# untitled.net
KiCad netlist of a schematic drawn in EAGLE
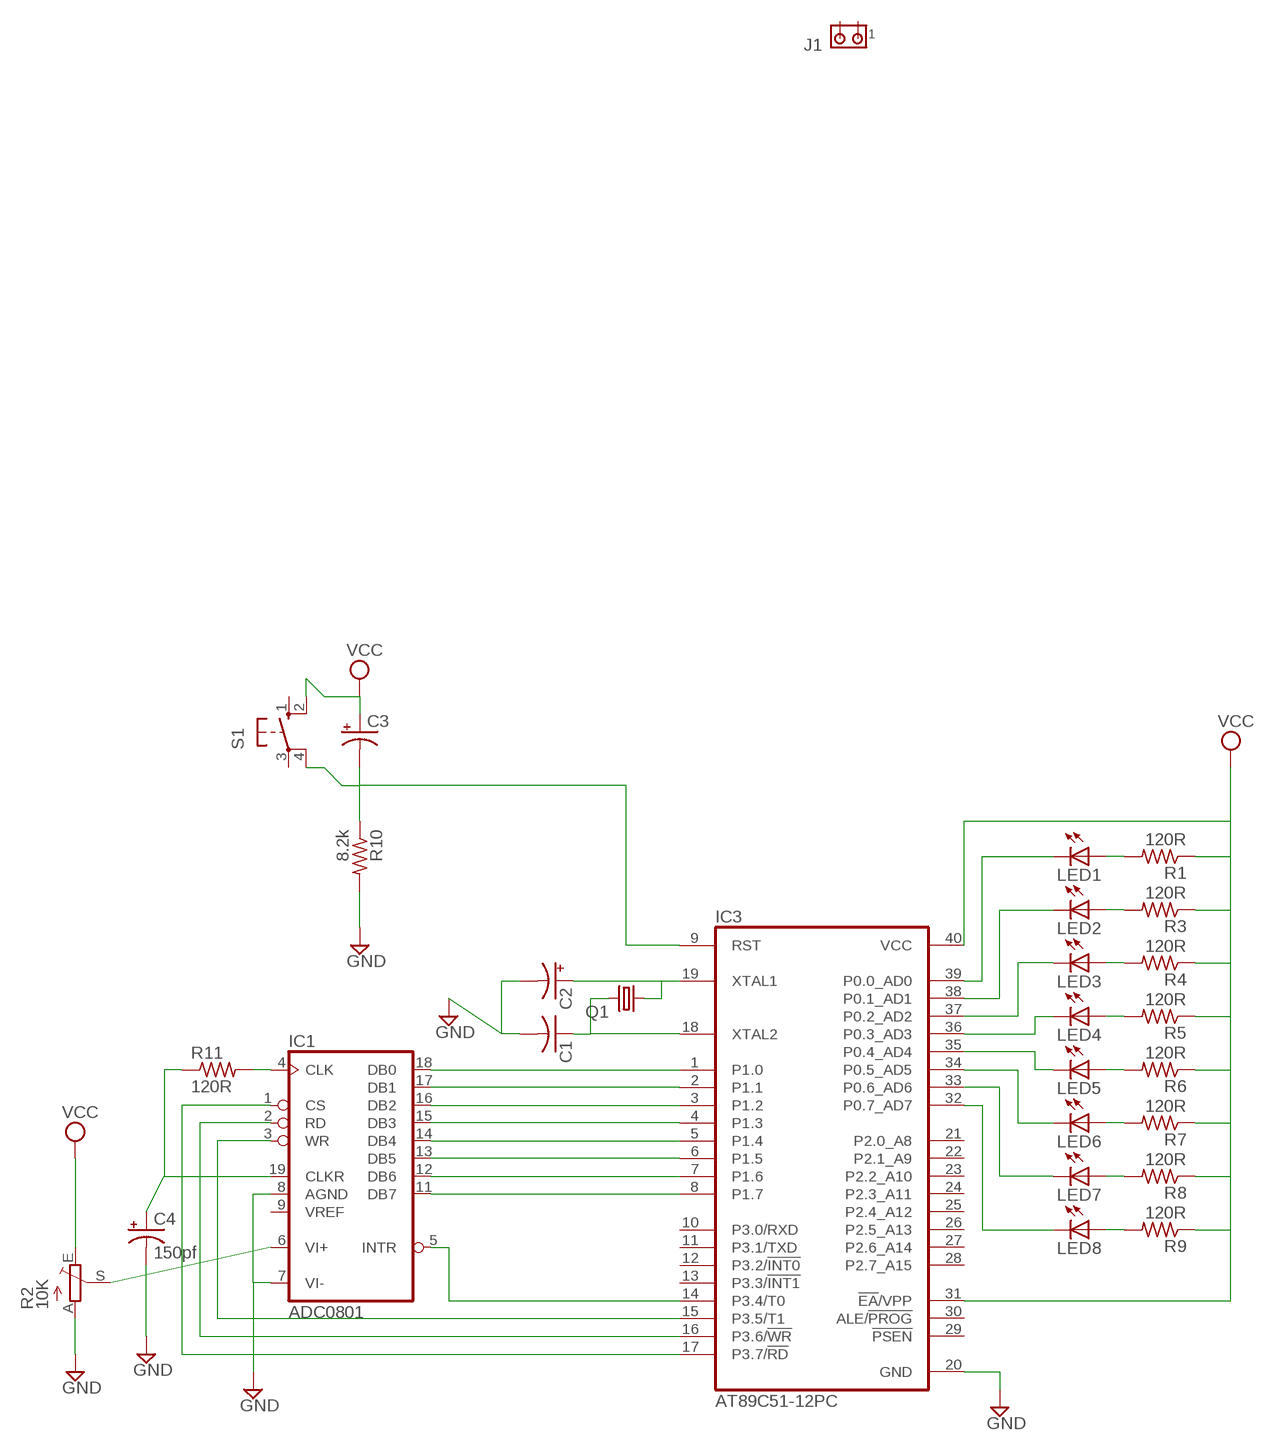
[diagram p0: schematic, sheet 1]

(export (version "E")
  (design (tool "Eeschema 10.0.6"))
  (components
    (comp (ref "C1")
      (value "C-US025-025X050")
      (footprint "eagle-import:C025-025X050")
      (libsource (lib "eagle-import") (part "C-US025-025X050"))
    )
    (comp (ref "C2")
      (value "CPOL-USE2.5-5V")
      (footprint "eagle-import:E2,5-4R")
      (libsource (lib "eagle-import") (part "CPOL-USE2.5-5V"))
    )
    (comp (ref "C3")
      (value "CPOL-USE2.5-5V")
      (footprint "eagle-import:E2,5-4R")
      (libsource (lib "eagle-import") (part "CPOL-USE2.5-5V"))
    )
    (comp (ref "C4")
      (value "150pf")
      (footprint "eagle-import:E2,5-4R")
      (libsource (lib "eagle-import") (part "CPOL-USE2.5-5V"))
    )
    (comp (ref "IC1")
      (value "ADC0801")
      (footprint "eagle-import:DIL20")
      (libsource (lib "eagle-import") (part "ADC0801"))
    )
    (comp (ref "IC3")
      (value "AT89C51-12PC")
      (footprint "eagle-import:DIL40")
      (libsource (lib "eagle-import") (part "AT89C51-PC12"))
    )
    (comp (ref "J1")
      (value "MTA02-100")
      (footprint "eagle-import:10X02MTA")
      (libsource (lib "eagle-import") (part "MTA02-100"))
    )
    (comp (ref "LED1")
      (value "LEDCHIP-LED0805")
      (footprint "eagle-import:CHIP-LED0805")
      (libsource (lib "eagle-import") (part "LEDCHIP-LED0805"))
    )
    (comp (ref "LED2")
      (value "LEDCHIP-LED0805")
      (footprint "eagle-import:CHIP-LED0805")
      (libsource (lib "eagle-import") (part "LEDCHIP-LED0805"))
    )
    (comp (ref "LED3")
      (value "LEDCHIP-LED0805")
      (footprint "eagle-import:CHIP-LED0805")
      (libsource (lib "eagle-import") (part "LEDCHIP-LED0805"))
    )
    (comp (ref "LED4")
      (value "LEDCHIP-LED0805")
      (footprint "eagle-import:CHIP-LED0805")
      (libsource (lib "eagle-import") (part "LEDCHIP-LED0805"))
    )
    (comp (ref "LED5")
      (value "LEDCHIP-LED0805")
      (footprint "eagle-import:CHIP-LED0805")
      (libsource (lib "eagle-import") (part "LEDCHIP-LED0805"))
    )
    (comp (ref "LED6")
      (value "LEDCHIP-LED0805")
      (footprint "eagle-import:CHIP-LED0805")
      (libsource (lib "eagle-import") (part "LEDCHIP-LED0805"))
    )
    (comp (ref "LED7")
      (value "LEDCHIP-LED0805")
      (footprint "eagle-import:CHIP-LED0805")
      (libsource (lib "eagle-import") (part "LEDCHIP-LED0805"))
    )
    (comp (ref "LED8")
      (value "LEDCHIP-LED0805")
      (footprint "eagle-import:CHIP-LED0805")
      (libsource (lib "eagle-import") (part "LEDCHIP-LED0805"))
    )
    (comp (ref "Q1")
      (value "CRYSTALTC26H")
      (footprint "eagle-import:TC26H")
      (libsource (lib "eagle-import") (part "CRYSTALTC26H"))
    )
    (comp (ref "R1")
      (value "120R")
      (footprint "eagle-import:R2512")
      (libsource (lib "eagle-import") (part "R-US_R2512"))
    )
    (comp (ref "R2")
      (value "10K")
      (footprint "eagle-import:B25U")
      (libsource (lib "eagle-import") (part "TRIM_EU-B25U"))
    )
    (comp (ref "R3")
      (value "120R")
      (footprint "eagle-import:R2512")
      (libsource (lib "eagle-import") (part "R-US_R2512"))
    )
    (comp (ref "R4")
      (value "120R")
      (footprint "eagle-import:R2512")
      (libsource (lib "eagle-import") (part "R-US_R2512"))
    )
    (comp (ref "R5")
      (value "120R")
      (footprint "eagle-import:R2512")
      (libsource (lib "eagle-import") (part "R-US_R2512"))
    )
    (comp (ref "R6")
      (value "120R")
      (footprint "eagle-import:R2512")
      (libsource (lib "eagle-import") (part "R-US_R2512"))
    )
    (comp (ref "R7")
      (value "120R")
      (footprint "eagle-import:R2512")
      (libsource (lib "eagle-import") (part "R-US_R2512"))
    )
    (comp (ref "R8")
      (value "120R")
      (footprint "eagle-import:R2512")
      (libsource (lib "eagle-import") (part "R-US_R2512"))
    )
    (comp (ref "R9")
      (value "120R")
      (footprint "eagle-import:R2512")
      (libsource (lib "eagle-import") (part "R-US_R2512"))
    )
    (comp (ref "R10")
      (value "8.2k")
      (footprint "eagle-import:R2512")
      (libsource (lib "eagle-import") (part "R-US_R2512"))
    )
    (comp (ref "R11")
      (value "120R")
      (footprint "eagle-import:R2512")
      (libsource (lib "eagle-import") (part "R-US_R2512"))
    )
    (comp (ref "S1")
      (value "10-XX")
      (footprint "eagle-import:B3F-10XX")
      (fields (field (name "MPN") "B3F-1000"))
      (libsource (lib "eagle-import") (part "10-XX"))
    )
  )
  (nets
    (net (code "1") (name "GND") (class "Default")
      (node (ref "C1") (pin "2") (pinfunction "2_2") (pintype "passive"))
      (node (ref "C2") (pin "-") (pinfunction "-_-") (pintype "passive"))
      (node (ref "C4") (pin "-") (pinfunction "-_-") (pintype "passive"))
      (node (ref "IC1") (pin "7") (pinfunction "VI-_7") (pintype "input"))
      (node (ref "IC1") (pin "8") (pinfunction "AGND_8") (pintype "input"))
      (node (ref "IC3") (pin "20") (pinfunction "GND_20") (pintype "power_in"))
      (node (ref "R10") (pin "2") (pinfunction "2_2") (pintype "passive"))
      (node (ref "R2") (pin "A") (pinfunction "A_A") (pintype "passive"))
    )
    (net (code "2") (name "Net-(IC1A-CLK)") (class "Default")
      (node (ref "IC1") (pin "4") (pinfunction "CLK_4") (pintype "input"))
      (node (ref "R11") (pin "2") (pinfunction "2_2") (pintype "passive"))
    )
    (net (code "3") (name "Net-(IC1A-CLKR)") (class "Default")
      (node (ref "C4") (pin "+") (pinfunction "+_+") (pintype "passive"))
      (node (ref "IC1") (pin "19") (pinfunction "CLKR_19") (pintype "input"))
      (node (ref "R11") (pin "1") (pinfunction "1_1") (pintype "passive"))
    )
    (net (code "4") (name "Net-(IC1A-CS)") (class "Default")
      (node (ref "IC1") (pin "1") (pinfunction "CS_1") (pintype "input"))
      (node (ref "IC3") (pin "17") (pinfunction "P3.7/~{RD}_17") (pintype "bidirectional"))
    )
    (net (code "5") (name "Net-(IC1A-DB0)") (class "Default")
      (node (ref "IC1") (pin "18") (pinfunction "DB0_18") (pintype "output"))
      (node (ref "IC3") (pin "1") (pinfunction "P1.0_1") (pintype "bidirectional"))
    )
    (net (code "6") (name "Net-(IC1A-DB1)") (class "Default")
      (node (ref "IC1") (pin "17") (pinfunction "DB1_17") (pintype "output"))
      (node (ref "IC3") (pin "2") (pinfunction "P1.1_2") (pintype "bidirectional"))
    )
    (net (code "7") (name "Net-(IC1A-DB2)") (class "Default")
      (node (ref "IC1") (pin "16") (pinfunction "DB2_16") (pintype "output"))
      (node (ref "IC3") (pin "3") (pinfunction "P1.2_3") (pintype "bidirectional"))
    )
    (net (code "8") (name "Net-(IC1A-DB3)") (class "Default")
      (node (ref "IC1") (pin "15") (pinfunction "DB3_15") (pintype "output"))
      (node (ref "IC3") (pin "4") (pinfunction "P1.3_4") (pintype "bidirectional"))
    )
    (net (code "9") (name "Net-(IC1A-DB4)") (class "Default")
      (node (ref "IC1") (pin "14") (pinfunction "DB4_14") (pintype "output"))
      (node (ref "IC3") (pin "5") (pinfunction "P1.4_5") (pintype "bidirectional"))
    )
    (net (code "10") (name "Net-(IC1A-DB5)") (class "Default")
      (node (ref "IC1") (pin "13") (pinfunction "DB5_13") (pintype "output"))
      (node (ref "IC3") (pin "6") (pinfunction "P1.5_6") (pintype "bidirectional"))
    )
    (net (code "11") (name "Net-(IC1A-DB6)") (class "Default")
      (node (ref "IC1") (pin "12") (pinfunction "DB6_12") (pintype "output"))
      (node (ref "IC3") (pin "7") (pinfunction "P1.6_7") (pintype "bidirectional"))
    )
    (net (code "12") (name "Net-(IC1A-DB7)") (class "Default")
      (node (ref "IC1") (pin "11") (pinfunction "DB7_11") (pintype "output"))
      (node (ref "IC3") (pin "8") (pinfunction "P1.7_8") (pintype "bidirectional"))
    )
    (net (code "13") (name "Net-(IC1A-INTR)") (class "Default")
      (node (ref "IC1") (pin "5") (pinfunction "INTR_5") (pintype "output"))
      (node (ref "IC3") (pin "14") (pinfunction "P3.4/T0_14") (pintype "bidirectional"))
    )
    (net (code "14") (name "Net-(IC1A-RD)") (class "Default")
      (node (ref "IC1") (pin "2") (pinfunction "RD_2") (pintype "input"))
      (node (ref "IC3") (pin "16") (pinfunction "P3.6/~{WR}_16") (pintype "bidirectional"))
    )
    (net (code "15") (name "Net-(IC1A-VI+)") (class "Default")
      (node (ref "IC1") (pin "6") (pinfunction "VI+_6") (pintype "input"))
      (node (ref "R2") (pin "S") (pinfunction "S_S") (pintype "passive"))
    )
    (net (code "16") (name "Net-(IC1A-WR)") (class "Default")
      (node (ref "IC1") (pin "3") (pinfunction "WR_3") (pintype "input"))
      (node (ref "IC3") (pin "15") (pinfunction "P3.5/T1_15") (pintype "bidirectional"))
    )
    (net (code "17") (name "Net-(IC3-P0.0_AD0)") (class "Default")
      (node (ref "IC3") (pin "39") (pinfunction "P0.0_AD0_39") (pintype "bidirectional"))
      (node (ref "LED1") (pin "C") (pinfunction "C_C") (pintype "passive"))
    )
    (net (code "18") (name "Net-(IC3-P0.1_AD1)") (class "Default")
      (node (ref "IC3") (pin "38") (pinfunction "P0.1_AD1_38") (pintype "bidirectional"))
      (node (ref "LED2") (pin "C") (pinfunction "C_C") (pintype "passive"))
    )
    (net (code "19") (name "Net-(IC3-P0.2_AD2)") (class "Default")
      (node (ref "IC3") (pin "37") (pinfunction "P0.2_AD2_37") (pintype "bidirectional"))
      (node (ref "LED3") (pin "C") (pinfunction "C_C") (pintype "passive"))
    )
    (net (code "20") (name "Net-(IC3-P0.3_AD3)") (class "Default")
      (node (ref "IC3") (pin "36") (pinfunction "P0.3_AD3_36") (pintype "bidirectional"))
      (node (ref "LED4") (pin "C") (pinfunction "C_C") (pintype "passive"))
    )
    (net (code "21") (name "Net-(IC3-P0.4_AD4)") (class "Default")
      (node (ref "IC3") (pin "35") (pinfunction "P0.4_AD4_35") (pintype "bidirectional"))
      (node (ref "LED5") (pin "C") (pinfunction "C_C") (pintype "passive"))
    )
    (net (code "22") (name "Net-(IC3-P0.5_AD5)") (class "Default")
      (node (ref "IC3") (pin "34") (pinfunction "P0.5_AD5_34") (pintype "bidirectional"))
      (node (ref "LED6") (pin "C") (pinfunction "C_C") (pintype "passive"))
    )
    (net (code "23") (name "Net-(IC3-P0.6_AD6)") (class "Default")
      (node (ref "IC3") (pin "33") (pinfunction "P0.6_AD6_33") (pintype "bidirectional"))
      (node (ref "LED7") (pin "C") (pinfunction "C_C") (pintype "passive"))
    )
    (net (code "24") (name "Net-(IC3-P0.7_AD7)") (class "Default")
      (node (ref "IC3") (pin "32") (pinfunction "P0.7_AD7_32") (pintype "bidirectional"))
      (node (ref "LED8") (pin "C") (pinfunction "C_C") (pintype "passive"))
    )
    (net (code "25") (name "Net-(IC3-RST)") (class "Default")
      (node (ref "C3") (pin "-") (pinfunction "-_-") (pintype "passive"))
      (node (ref "IC3") (pin "9") (pinfunction "RST_9") (pintype "input"))
      (node (ref "R10") (pin "1") (pinfunction "1_1") (pintype "passive"))
      (node (ref "S1") (pin "4") (pinfunction "P1_4") (pintype "passive"))
    )
    (net (code "26") (name "Net-(IC3-XTAL1)") (class "Default")
      (node (ref "C2") (pin "+") (pinfunction "+_+") (pintype "passive"))
      (node (ref "IC3") (pin "19") (pinfunction "XTAL1_19") (pintype "input"))
      (node (ref "Q1") (pin "1") (pinfunction "1_1") (pintype "passive"))
    )
    (net (code "27") (name "Net-(IC3-XTAL2)") (class "Default")
      (node (ref "C1") (pin "1") (pinfunction "1_1") (pintype "passive"))
      (node (ref "IC3") (pin "18") (pinfunction "XTAL2_18") (pintype "input"))
      (node (ref "Q1") (pin "2") (pinfunction "2_2") (pintype "passive"))
    )
    (net (code "28") (name "Net-(LED1-PadA)") (class "Default")
      (node (ref "LED1") (pin "A") (pinfunction "A_A") (pintype "passive"))
      (node (ref "R1") (pin "2") (pinfunction "2_2") (pintype "passive"))
    )
    (net (code "29") (name "Net-(LED2-PadA)") (class "Default")
      (node (ref "LED2") (pin "A") (pinfunction "A_A") (pintype "passive"))
      (node (ref "R3") (pin "2") (pinfunction "2_2") (pintype "passive"))
    )
    (net (code "30") (name "Net-(LED3-PadA)") (class "Default")
      (node (ref "LED3") (pin "A") (pinfunction "A_A") (pintype "passive"))
      (node (ref "R4") (pin "2") (pinfunction "2_2") (pintype "passive"))
    )
    (net (code "31") (name "Net-(LED4-PadA)") (class "Default")
      (node (ref "LED4") (pin "A") (pinfunction "A_A") (pintype "passive"))
      (node (ref "R5") (pin "2") (pinfunction "2_2") (pintype "passive"))
    )
    (net (code "32") (name "Net-(LED5-PadA)") (class "Default")
      (node (ref "LED5") (pin "A") (pinfunction "A_A") (pintype "passive"))
      (node (ref "R6") (pin "2") (pinfunction "2_2") (pintype "passive"))
    )
    (net (code "33") (name "Net-(LED6-PadA)") (class "Default")
      (node (ref "LED6") (pin "A") (pinfunction "A_A") (pintype "passive"))
      (node (ref "R7") (pin "2") (pinfunction "2_2") (pintype "passive"))
    )
    (net (code "34") (name "Net-(LED7-PadA)") (class "Default")
      (node (ref "LED7") (pin "A") (pinfunction "A_A") (pintype "passive"))
      (node (ref "R8") (pin "2") (pinfunction "2_2") (pintype "passive"))
    )
    (net (code "35") (name "Net-(LED8-PadA)") (class "Default")
      (node (ref "LED8") (pin "A") (pinfunction "A_A") (pintype "passive"))
      (node (ref "R9") (pin "2") (pinfunction "2_2") (pintype "passive"))
    )
    (net (code "36") (name "VCC") (class "Default")
      (node (ref "C3") (pin "+") (pinfunction "+_+") (pintype "passive"))
      (node (ref "IC3") (pin "31") (pinfunction "~{EA}/VPP_31") (pintype "input"))
      (node (ref "IC3") (pin "40") (pinfunction "VCC_40") (pintype "power_in"))
      (node (ref "R1") (pin "1") (pinfunction "1_1") (pintype "passive"))
      (node (ref "R2") (pin "E") (pinfunction "E_E") (pintype "passive"))
      (node (ref "R3") (pin "1") (pinfunction "1_1") (pintype "passive"))
      (node (ref "R4") (pin "1") (pinfunction "1_1") (pintype "passive"))
      (node (ref "R5") (pin "1") (pinfunction "1_1") (pintype "passive"))
      (node (ref "R6") (pin "1") (pinfunction "1_1") (pintype "passive"))
      (node (ref "R7") (pin "1") (pinfunction "1_1") (pintype "passive"))
      (node (ref "R8") (pin "1") (pinfunction "1_1") (pintype "passive"))
      (node (ref "R9") (pin "1") (pinfunction "1_1") (pintype "passive"))
      (node (ref "S1") (pin "2") (pinfunction "S1_2") (pintype "passive"))
    )
    (net (code "37") (name "unconnected-(IC1A-VREF-Pad9)") (class "Default")
      (node (ref "IC1") (pin "9") (pinfunction "VREF_9") (pintype "input"))
    )
    (net (code "38") (name "unconnected-(IC3-ALE{slash}~{PROG}-Pad30)") (class "Default")
      (node (ref "IC3") (pin "30") (pinfunction "ALE/~{PROG}_30") (pintype "output"))
    )
    (net (code "39") (name "unconnected-(IC3-P2.0_A8-Pad21)") (class "Default")
      (node (ref "IC3") (pin "21") (pinfunction "P2.0_A8_21") (pintype "bidirectional"))
    )
    (net (code "40") (name "unconnected-(IC3-P2.1_A9-Pad22)") (class "Default")
      (node (ref "IC3") (pin "22") (pinfunction "P2.1_A9_22") (pintype "bidirectional"))
    )
    (net (code "41") (name "unconnected-(IC3-P2.2_A10-Pad23)") (class "Default")
      (node (ref "IC3") (pin "23") (pinfunction "P2.2_A10_23") (pintype "bidirectional"))
    )
    (net (code "42") (name "unconnected-(IC3-P2.3_A11-Pad24)") (class "Default")
      (node (ref "IC3") (pin "24") (pinfunction "P2.3_A11_24") (pintype "bidirectional"))
    )
    (net (code "43") (name "unconnected-(IC3-P2.4_A12-Pad25)") (class "Default")
      (node (ref "IC3") (pin "25") (pinfunction "P2.4_A12_25") (pintype "bidirectional"))
    )
    (net (code "44") (name "unconnected-(IC3-P2.5_A13-Pad26)") (class "Default")
      (node (ref "IC3") (pin "26") (pinfunction "P2.5_A13_26") (pintype "bidirectional"))
    )
    (net (code "45") (name "unconnected-(IC3-P2.6_A14-Pad27)") (class "Default")
      (node (ref "IC3") (pin "27") (pinfunction "P2.6_A14_27") (pintype "bidirectional"))
    )
    (net (code "46") (name "unconnected-(IC3-P2.7_A15-Pad28)") (class "Default")
      (node (ref "IC3") (pin "28") (pinfunction "P2.7_A15_28") (pintype "bidirectional"))
    )
    (net (code "47") (name "unconnected-(IC3-P3.0{slash}RXD-Pad10)") (class "Default")
      (node (ref "IC3") (pin "10") (pinfunction "P3.0/RXD_10") (pintype "bidirectional"))
    )
    (net (code "48") (name "unconnected-(IC3-P3.1{slash}TXD-Pad11)") (class "Default")
      (node (ref "IC3") (pin "11") (pinfunction "P3.1/TXD_11") (pintype "bidirectional"))
    )
    (net (code "49") (name "unconnected-(IC3-P3.2{slash}~{INT0}-Pad12)") (class "Default")
      (node (ref "IC3") (pin "12") (pinfunction "P3.2/~{INT0}_12") (pintype "bidirectional"))
    )
    (net (code "50") (name "unconnected-(IC3-P3.3{slash}~{INT1}-Pad13)") (class "Default")
      (node (ref "IC3") (pin "13") (pinfunction "P3.3/~{INT1}_13") (pintype "bidirectional"))
    )
    (net (code "51") (name "unconnected-(IC3-~{PSEN}-Pad29)") (class "Default")
      (node (ref "IC3") (pin "29") (pinfunction "~{PSEN}_29") (pintype "output"))
    )
    (net (code "52") (name "unconnected-(J1-Pad1)") (class "Default")
      (node (ref "J1") (pin "1") (pinfunction "1_1") (pintype "passive"))
    )
    (net (code "53") (name "unconnected-(J1-Pad2)") (class "Default")
      (node (ref "J1") (pin "2") (pinfunction "2_2") (pintype "passive"))
    )
    (net (code "54") (name "unconnected-(S1-P-Pad3)") (class "Default")
      (node (ref "S1") (pin "3") (pinfunction "P_3") (pintype "passive"))
    )
    (net (code "55") (name "unconnected-(S1-S-Pad1)") (class "Default")
      (node (ref "S1") (pin "1") (pinfunction "S_1") (pintype "passive"))
    )
  )
)
